# HV_DAC_8ch-DIOT.net
KiCad netlist of a schematic drawn in Altium Designer
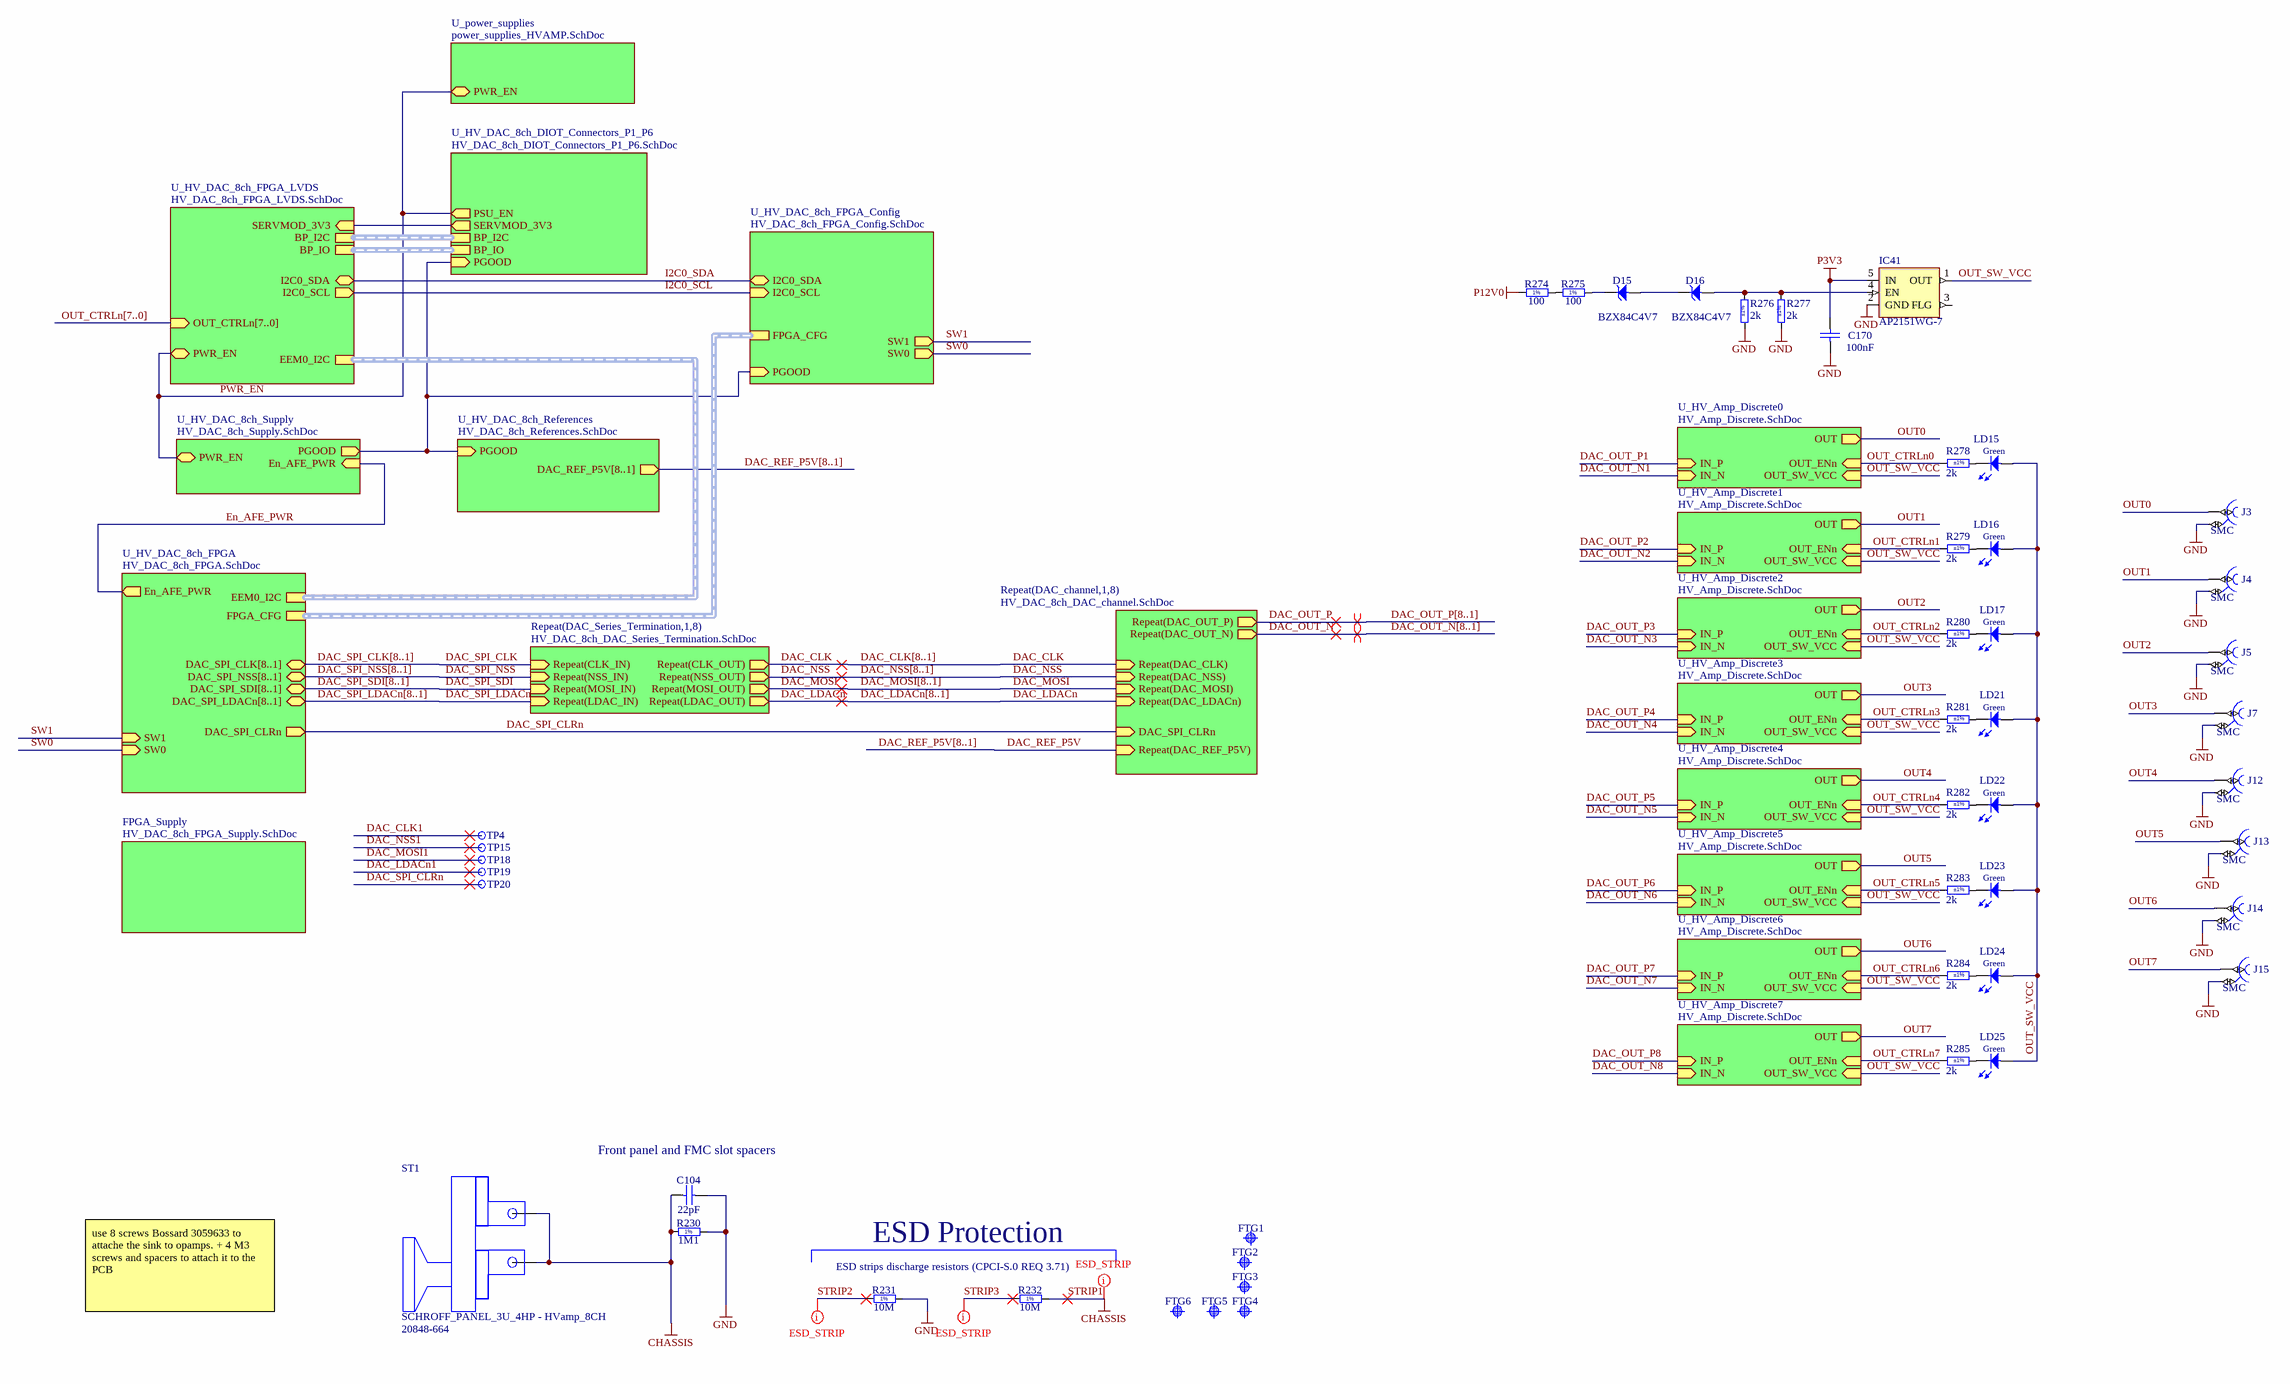
[diagram p0: HV_DAC_8ch-DIOT.schdoc]

(export (version "E")
  (design (tool "Eeschema 10.0.6"))
  (components
    (comp (ref "C104")
      (value "22pF")
      (footprint "CAPC1005X55N")
      (description "Non-polarised capacitor")
      (fields
        (field (name "PART NUMBER") "CC0402_22PF_50V_5%_C0G")
        (field (name "VOLTAGE") "50V")
        (field (name "AUTHOR") "CERN DEM JLC")
      )
      (libsource (lib "Capacitors") (part "Capacitor - non polarized"))
    )
    (comp (ref "C170")
      (value "100nF")
      (footprint "CAPC1005X55N")
      (description "Non-polarised capacitor")
      (fields
        (field (name "PART NUMBER") "CC0402_100NF_16V_10%_X5R")
        (field (name "VOLTAGE") "16V")
        (field (name "AUTHOR") "CERN DEM JLC")
      )
      (libsource (lib "Capacitors") (part "Capacitor - non polarized"))
    )
    (comp (ref "D15")
      (value "BZX84C4V7")
      (footprint "SOT95P240X130-3N")
      (description "Diode Zener Anode Pin 1 Cathode Pin 3 (Pas de pin 2)")
      (fields
        (field (name "VOLTAGE") "4V7")
        (field (name "POWER") "350mW")
        (field (name "AUTHOR") "CERN DEM JLC")
      )
      (libsource (lib "ICs And Semiconductors") (part "Diode Zener A1C3"))
    )
    (comp (ref "D16")
      (value "BZX84C4V7")
      (footprint "SOT95P240X130-3N")
      (description "Diode Zener Anode Pin 1 Cathode Pin 3 (Pas de pin 2)")
      (fields
        (field (name "VOLTAGE") "4V7")
        (field (name "POWER") "350mW")
        (field (name "AUTHOR") "CERN DEM JLC")
      )
      (libsource (lib "ICs And Semiconductors") (part "Diode Zener A1C3"))
    )
    (comp (ref "FTG1")
      (value "Use only in PCB")
      (footprint "FIDUCIAL_TOP_C100-200")
      (description "Fiducial Target")
      (fields (field (name "PART NUMBER") "FIDUCIAL_TARGET_C100-200") (field (name "AUTHOR") "CERN DEM JLC"))
      (libsource (lib "Eletro-mechanical") (part "Fiducial Target"))
    )
    (comp (ref "FTG2")
      (value "Use only in PCB")
      (footprint "FIDUCIAL_TOP_S100-200")
      (description "Fiducial Target")
      (fields (field (name "PART NUMBER") "FIDUCIAL_TARGET_S100-200") (field (name "AUTHOR") "CERN DEM JLC"))
      (libsource (lib "Eletro-mechanical") (part "Fiducial Target"))
    )
    (comp (ref "FTG3")
      (value "Use only in PCB")
      (footprint "FIDUCIAL_TOP_S100-200")
      (description "Fiducial Target")
      (fields (field (name "PART NUMBER") "FIDUCIAL_TARGET_S100-200") (field (name "AUTHOR") "CERN DEM JLC"))
      (libsource (lib "Eletro-mechanical") (part "Fiducial Target"))
    )
    (comp (ref "FTG4")
      (value "Use only in PCB")
      (footprint "FIDUCIAL_TOP_S100-200")
      (description "Fiducial Target")
      (fields (field (name "PART NUMBER") "FIDUCIAL_TARGET_S100-200") (field (name "AUTHOR") "CERN DEM JLC"))
      (libsource (lib "Eletro-mechanical") (part "Fiducial Target"))
    )
    (comp (ref "FTG5")
      (value "Use only in PCB")
      (footprint "FIDUCIAL_TOP_S100-200")
      (description "Fiducial Target")
      (fields (field (name "PART NUMBER") "FIDUCIAL_TARGET_S100-200") (field (name "AUTHOR") "CERN DEM JLC"))
      (libsource (lib "Eletro-mechanical") (part "Fiducial Target"))
    )
    (comp (ref "FTG6")
      (value "Use only in PCB")
      (footprint "FIDUCIAL_TOP_S100-200")
      (description "Fiducial Target")
      (fields (field (name "PART NUMBER") "FIDUCIAL_TARGET_S100-200") (field (name "AUTHOR") "CERN DEM JLC"))
      (libsource (lib "Eletro-mechanical") (part "Fiducial Target"))
    )
    (comp (ref "IC41")
      (value "AP2151WG-7")
      (footprint "SOT23-5")
      (description "0.5A SINGLE CHANNEL CURRENT- LIMITED POWER Switch")
      (libsource (lib "ICs_Analog_Interfaces") (part "IFC_AP2151"))
    )
    (comp (ref "J3")
      (value "SMC")
      (footprint "JOHNSON_131-6701-341")
      (fields
        (field (name "PART NUMBER") "JOHNSON_131-6701-341")
        (field (name "MANUFACTURER") "JOHNSON")
        (field (name "MANUFACTURER PART NUMBER") "131-6701-341")
        (field (name "AUTHOR") "CERN DEM JLC")
      )
      (libsource (lib "Connectors") (part "Coax_1Female_1Shield"))
    )
    (comp (ref "J4")
      (value "SMC")
      (footprint "JOHNSON_131-6701-341")
      (fields
        (field (name "PART NUMBER") "JOHNSON_131-6701-341")
        (field (name "MANUFACTURER") "JOHNSON")
        (field (name "MANUFACTURER PART NUMBER") "131-6701-341")
        (field (name "AUTHOR") "CERN DEM JLC")
      )
      (libsource (lib "Connectors") (part "Coax_1Female_1Shield"))
    )
    (comp (ref "J5")
      (value "SMC")
      (footprint "JOHNSON_131-6701-341")
      (fields
        (field (name "PART NUMBER") "JOHNSON_131-6701-341")
        (field (name "MANUFACTURER") "JOHNSON")
        (field (name "MANUFACTURER PART NUMBER") "131-6701-341")
        (field (name "AUTHOR") "CERN DEM JLC")
      )
      (libsource (lib "Connectors") (part "Coax_1Female_1Shield"))
    )
    (comp (ref "J7")
      (value "SMC")
      (footprint "JOHNSON_131-6701-341")
      (fields
        (field (name "PART NUMBER") "JOHNSON_131-6701-341")
        (field (name "MANUFACTURER") "JOHNSON")
        (field (name "MANUFACTURER PART NUMBER") "131-6701-341")
        (field (name "AUTHOR") "CERN DEM JLC")
      )
      (libsource (lib "Connectors") (part "Coax_1Female_1Shield"))
    )
    (comp (ref "J12")
      (value "SMC")
      (footprint "JOHNSON_131-6701-341")
      (fields
        (field (name "PART NUMBER") "JOHNSON_131-6701-341")
        (field (name "MANUFACTURER") "JOHNSON")
        (field (name "MANUFACTURER PART NUMBER") "131-6701-341")
        (field (name "AUTHOR") "CERN DEM JLC")
      )
      (libsource (lib "Connectors") (part "Coax_1Female_1Shield"))
    )
    (comp (ref "J13")
      (value "SMC")
      (footprint "JOHNSON_131-6701-341")
      (fields
        (field (name "PART NUMBER") "JOHNSON_131-6701-341")
        (field (name "MANUFACTURER") "JOHNSON")
        (field (name "MANUFACTURER PART NUMBER") "131-6701-341")
        (field (name "AUTHOR") "CERN DEM JLC")
      )
      (libsource (lib "Connectors") (part "Coax_1Female_1Shield"))
    )
    (comp (ref "J14")
      (value "SMC")
      (footprint "JOHNSON_131-6701-341")
      (fields
        (field (name "PART NUMBER") "JOHNSON_131-6701-341")
        (field (name "MANUFACTURER") "JOHNSON")
        (field (name "MANUFACTURER PART NUMBER") "131-6701-341")
        (field (name "AUTHOR") "CERN DEM JLC")
      )
      (libsource (lib "Connectors") (part "Coax_1Female_1Shield"))
    )
    (comp (ref "J15")
      (value "SMC")
      (footprint "JOHNSON_131-6701-341")
      (fields
        (field (name "PART NUMBER") "JOHNSON_131-6701-341")
        (field (name "MANUFACTURER") "JOHNSON")
        (field (name "MANUFACTURER PART NUMBER") "131-6701-341")
        (field (name "AUTHOR") "CERN DEM JLC")
      )
      (libsource (lib "Connectors") (part "Coax_1Female_1Shield"))
    )
    (comp (ref "LD15")
      (value "Green")
      (footprint "LED_AVAGO_HSME-C120")
      (description "LED Green 1C 2A")
      (fields
        (field (name "PART NUMBER") "LED_AVAGO_HSME-C120")
        (field (name "MANUFACTURER") "AVAGO TECHNOLOGIES")
        (field (name "AUTHOR") "CERN DEM JMW")
      )
      (libsource (lib "ICs And Semiconductors") (part "LED Green 1C 2A"))
    )
    (comp (ref "LD16")
      (value "Green")
      (footprint "LED_AVAGO_HSME-C120")
      (description "LED Green 1C 2A")
      (fields
        (field (name "PART NUMBER") "LED_AVAGO_HSME-C120")
        (field (name "MANUFACTURER") "AVAGO TECHNOLOGIES")
        (field (name "AUTHOR") "CERN DEM JMW")
      )
      (libsource (lib "ICs And Semiconductors") (part "LED Green 1C 2A"))
    )
    (comp (ref "LD17")
      (value "Green")
      (footprint "LED_AVAGO_HSME-C120")
      (description "LED Green 1C 2A")
      (fields
        (field (name "PART NUMBER") "LED_AVAGO_HSME-C120")
        (field (name "MANUFACTURER") "AVAGO TECHNOLOGIES")
        (field (name "AUTHOR") "CERN DEM JMW")
      )
      (libsource (lib "ICs And Semiconductors") (part "LED Green 1C 2A"))
    )
    (comp (ref "LD21")
      (value "Green")
      (footprint "LED_AVAGO_HSME-C120")
      (description "LED Green 1C 2A")
      (fields
        (field (name "PART NUMBER") "LED_AVAGO_HSME-C120")
        (field (name "MANUFACTURER") "AVAGO TECHNOLOGIES")
        (field (name "AUTHOR") "CERN DEM JMW")
      )
      (libsource (lib "ICs And Semiconductors") (part "LED Green 1C 2A"))
    )
    (comp (ref "LD22")
      (value "Green")
      (footprint "LED_AVAGO_HSME-C120")
      (description "LED Green 1C 2A")
      (fields
        (field (name "PART NUMBER") "LED_AVAGO_HSME-C120")
        (field (name "MANUFACTURER") "AVAGO TECHNOLOGIES")
        (field (name "AUTHOR") "CERN DEM JMW")
      )
      (libsource (lib "ICs And Semiconductors") (part "LED Green 1C 2A"))
    )
    (comp (ref "LD23")
      (value "Green")
      (footprint "LED_AVAGO_HSME-C120")
      (description "LED Green 1C 2A")
      (fields
        (field (name "PART NUMBER") "LED_AVAGO_HSME-C120")
        (field (name "MANUFACTURER") "AVAGO TECHNOLOGIES")
        (field (name "AUTHOR") "CERN DEM JMW")
      )
      (libsource (lib "ICs And Semiconductors") (part "LED Green 1C 2A"))
    )
    (comp (ref "LD24")
      (value "Green")
      (footprint "LED_AVAGO_HSME-C120")
      (description "LED Green 1C 2A")
      (fields
        (field (name "PART NUMBER") "LED_AVAGO_HSME-C120")
        (field (name "MANUFACTURER") "AVAGO TECHNOLOGIES")
        (field (name "AUTHOR") "CERN DEM JMW")
      )
      (libsource (lib "ICs And Semiconductors") (part "LED Green 1C 2A"))
    )
    (comp (ref "LD25")
      (value "Green")
      (footprint "LED_AVAGO_HSME-C120")
      (description "LED Green 1C 2A")
      (fields
        (field (name "PART NUMBER") "LED_AVAGO_HSME-C120")
        (field (name "MANUFACTURER") "AVAGO TECHNOLOGIES")
        (field (name "AUTHOR") "CERN DEM JMW")
      )
      (libsource (lib "ICs And Semiconductors") (part "LED Green 1C 2A"))
    )
    (comp (ref "R230")
      (value "1M1")
      (footprint "RESC2012X60N")
      (description "Resistor - 1%")
      (fields
        (field (name "PART NUMBER") "R0805_1M1_1%_0.125W_100PPM")
        (field (name "POWER") "0.125W")
        (field (name "AUTHOR") "CERN DEM JLC")
      )
      (libsource (lib "") (part "Resistor - 1%_1"))
    )
    (comp (ref "R231")
      (value "10M")
      (footprint "RESC2113X55N")
      (description "Resistor - 1%")
      (fields
        (field (name "PART NUMBER") "R0805_10M_1%_0.125W_100PPM_VISHAY_CRCW e3")
        (field (name "POWER") "0.125W")
        (field (name "AUTHOR") "CERN DEM BC")
      )
      (libsource (lib "") (part "Resistor - 1%_1"))
    )
    (comp (ref "R232")
      (value "10M")
      (footprint "RESC2113X55N")
      (description "Resistor - 1%")
      (fields
        (field (name "PART NUMBER") "R0805_10M_1%_0.125W_100PPM_VISHAY_CRCW e3")
        (field (name "POWER") "0.125W")
        (field (name "AUTHOR") "CERN DEM BC")
      )
      (libsource (lib "") (part "Resistor - 1%_1"))
    )
    (comp (ref "R274")
      (value "100")
      (footprint "RESC1005X40N")
      (description "Resistor - 1%")
      (fields
        (field (name "PART NUMBER") "R0402_100R_1%_0.0625W_100PPM")
        (field (name "POWER") "0.0625W")
        (field (name "AUTHOR") "CERN DEM JLC")
      )
      (libsource (lib "Resistors") (part "Resistor - 1%"))
    )
    (comp (ref "R275")
      (value "100")
      (footprint "RESC1005X40N")
      (description "Resistor - 1%")
      (fields
        (field (name "PART NUMBER") "R0402_100R_1%_0.0625W_100PPM")
        (field (name "POWER") "0.0625W")
        (field (name "AUTHOR") "CERN DEM JLC")
      )
      (libsource (lib "Resistors") (part "Resistor - 1%"))
    )
    (comp (ref "R276")
      (value "2k")
      (footprint "RESC1005X40N")
      (description "Resistor - 1%")
      (fields
        (field (name "PART NUMBER") "R0402_2K_1%_0.0625W_100PPM")
        (field (name "POWER") "0.0625W")
        (field (name "TOLERANCE") "±1%")
        (field (name "AUTHOR") "CERN DEM JLC")
      )
      (libsource (lib "Resistors") (part "Resistor - 1%"))
    )
    (comp (ref "R277")
      (value "2k")
      (footprint "RESC1005X40N")
      (description "Resistor - 1%")
      (fields
        (field (name "PART NUMBER") "R0402_2K_1%_0.0625W_100PPM")
        (field (name "POWER") "0.0625W")
        (field (name "TOLERANCE") "±1%")
        (field (name "AUTHOR") "CERN DEM JLC")
      )
      (libsource (lib "Resistors") (part "Resistor - 1%"))
    )
    (comp (ref "R278")
      (value "2k")
      (footprint "RESC1005X40N")
      (description "Resistor - 1%")
      (fields
        (field (name "PART NUMBER") "R0402_2K_1%_0.0625W_100PPM")
        (field (name "POWER") "0.0625W")
        (field (name "TOLERANCE") "±1%")
        (field (name "AUTHOR") "CERN DEM JLC")
      )
      (libsource (lib "Resistors") (part "Resistor - 1%"))
    )
    (comp (ref "R279")
      (value "2k")
      (footprint "RESC1005X40N")
      (description "Resistor - 1%")
      (fields
        (field (name "PART NUMBER") "R0402_2K_1%_0.0625W_100PPM")
        (field (name "POWER") "0.0625W")
        (field (name "TOLERANCE") "±1%")
        (field (name "AUTHOR") "CERN DEM JLC")
      )
      (libsource (lib "Resistors") (part "Resistor - 1%"))
    )
    (comp (ref "R280")
      (value "2k")
      (footprint "RESC1005X40N")
      (description "Resistor - 1%")
      (fields
        (field (name "PART NUMBER") "R0402_2K_1%_0.0625W_100PPM")
        (field (name "POWER") "0.0625W")
        (field (name "TOLERANCE") "±1%")
        (field (name "AUTHOR") "CERN DEM JLC")
      )
      (libsource (lib "Resistors") (part "Resistor - 1%"))
    )
    (comp (ref "R281")
      (value "2k")
      (footprint "RESC1005X40N")
      (description "Resistor - 1%")
      (fields
        (field (name "PART NUMBER") "R0402_2K_1%_0.0625W_100PPM")
        (field (name "POWER") "0.0625W")
        (field (name "TOLERANCE") "±1%")
        (field (name "AUTHOR") "CERN DEM JLC")
      )
      (libsource (lib "Resistors") (part "Resistor - 1%"))
    )
    (comp (ref "R282")
      (value "2k")
      (footprint "RESC1005X40N")
      (description "Resistor - 1%")
      (fields
        (field (name "PART NUMBER") "R0402_2K_1%_0.0625W_100PPM")
        (field (name "POWER") "0.0625W")
        (field (name "TOLERANCE") "±1%")
        (field (name "AUTHOR") "CERN DEM JLC")
      )
      (libsource (lib "Resistors") (part "Resistor - 1%"))
    )
    (comp (ref "R283")
      (value "2k")
      (footprint "RESC1005X40N")
      (description "Resistor - 1%")
      (fields
        (field (name "PART NUMBER") "R0402_2K_1%_0.0625W_100PPM")
        (field (name "POWER") "0.0625W")
        (field (name "TOLERANCE") "±1%")
        (field (name "AUTHOR") "CERN DEM JLC")
      )
      (libsource (lib "Resistors") (part "Resistor - 1%"))
    )
    (comp (ref "R284")
      (value "2k")
      (footprint "RESC1005X40N")
      (description "Resistor - 1%")
      (fields
        (field (name "PART NUMBER") "R0402_2K_1%_0.0625W_100PPM")
        (field (name "POWER") "0.0625W")
        (field (name "TOLERANCE") "±1%")
        (field (name "AUTHOR") "CERN DEM JLC")
      )
      (libsource (lib "Resistors") (part "Resistor - 1%"))
    )
    (comp (ref "R285")
      (value "2k")
      (footprint "RESC1005X40N")
      (description "Resistor - 1%")
      (fields
        (field (name "PART NUMBER") "R0402_2K_1%_0.0625W_100PPM")
        (field (name "POWER") "0.0625W")
        (field (name "TOLERANCE") "±1%")
        (field (name "AUTHOR") "CERN DEM JLC")
      )
      (libsource (lib "Resistors") (part "Resistor - 1%"))
    )
    (comp (ref "ST1")
      (value "SCHROFF_PANEL_3U_4HP - HVamp_8CH")
      (footprint "SCHROFF_PANEL_3U_4HP - HVamp_8CH")
      (description "Schroff 3HP 4U EUROCARD Panel")
      (fields
        (field (name "MANUFACTURER") "Schroff")
        (field (name "MANUFACTURER PART NUMBER") "20818-017")
        (field (name "MANUFACTURER PART NUMBER 2") "20848-664")
      )
      (libsource (lib "Mechanical") (part "SCHROFF_PANEL_3U_4HP - HVamp_8CH"))
    )
    (comp (ref "TP4")
      (value "Test Point")
      (footprint "TPS127")
      (fields (field (name "PART NUMBER") "SMD_PAD_1.27X1.27MM") (field (name "AUTHOR") "CERN DEM JLC"))
      (libsource (lib "Eletro-mechanical") (part "Test Point"))
    )
    (comp (ref "TP15")
      (value "Test Point")
      (footprint "TPS127")
      (fields (field (name "PART NUMBER") "SMD_PAD_1.27X1.27MM") (field (name "AUTHOR") "CERN DEM JLC"))
      (libsource (lib "Eletro-mechanical") (part "Test Point"))
    )
    (comp (ref "TP18")
      (value "Test Point")
      (footprint "TPS127")
      (fields (field (name "PART NUMBER") "SMD_PAD_1.27X1.27MM") (field (name "AUTHOR") "CERN DEM JLC"))
      (libsource (lib "Eletro-mechanical") (part "Test Point"))
    )
    (comp (ref "TP19")
      (value "Test Point")
      (footprint "TPS127")
      (fields (field (name "PART NUMBER") "SMD_PAD_1.27X1.27MM") (field (name "AUTHOR") "CERN DEM JLC"))
      (libsource (lib "Eletro-mechanical") (part "Test Point"))
    )
    (comp (ref "TP20")
      (value "Test Point")
      (footprint "TPS127")
      (fields (field (name "PART NUMBER") "SMD_PAD_1.27X1.27MM") (field (name "AUTHOR") "CERN DEM JLC"))
      (libsource (lib "Eletro-mechanical") (part "Test Point"))
    )
  )
  (nets
    (net (code "72") (name "/DAC_CLK1") (class "Default")
      (node (ref "TP4") (pin "1") (pinfunction "1_1") (pintype "bidirectional"))
    )
    (net (code "75") (name "/DAC_LDACn1") (class "Default")
      (node (ref "TP19") (pin "1") (pinfunction "1_1") (pintype "bidirectional"))
    )
    (net (code "78") (name "/DAC_MOSI1") (class "Default")
      (node (ref "TP18") (pin "1") (pinfunction "1_1") (pintype "bidirectional"))
    )
    (net (code "81") (name "/DAC_NSS1") (class "Default")
      (node (ref "TP15") (pin "1") (pinfunction "1_1") (pintype "bidirectional"))
    )
    (net (code "107") (name "/DAC_SPI_CLRn") (class "Default")
      (node (ref "TP20") (pin "1") (pinfunction "1_1") (pintype "bidirectional"))
    )
    (net (code "119") (name "/OUT0") (class "Default")
      (node (ref "J3") (pin "1") (pinfunction "1_1") (pintype "bidirectional"))
    )
    (net (code "120") (name "/OUT1") (class "Default")
      (node (ref "J4") (pin "1") (pinfunction "1_1") (pintype "bidirectional"))
    )
    (net (code "121") (name "/OUT2") (class "Default")
      (node (ref "J5") (pin "1") (pinfunction "1_1") (pintype "bidirectional"))
    )
    (net (code "122") (name "/OUT3") (class "Default")
      (node (ref "J7") (pin "1") (pinfunction "1_1") (pintype "bidirectional"))
    )
    (net (code "123") (name "/OUT4") (class "Default")
      (node (ref "J12") (pin "1") (pinfunction "1_1") (pintype "bidirectional"))
    )
    (net (code "124") (name "/OUT5") (class "Default")
      (node (ref "J13") (pin "1") (pinfunction "1_1") (pintype "bidirectional"))
    )
    (net (code "125") (name "/OUT6") (class "Default")
      (node (ref "J14") (pin "1") (pinfunction "1_1") (pintype "bidirectional"))
    )
    (net (code "126") (name "/OUT7") (class "Default")
      (node (ref "J15") (pin "1") (pinfunction "1_1") (pintype "bidirectional"))
    )
    (net (code "127") (name "/OUT_CTRLn0") (class "Default")
      (node (ref "R278") (pin "2") (pinfunction "2_2") (pintype "passive"))
    )
    (net (code "128") (name "/OUT_CTRLn1") (class "Default")
      (node (ref "R279") (pin "2") (pinfunction "2_2") (pintype "passive"))
    )
    (net (code "129") (name "/OUT_CTRLn2") (class "Default")
      (node (ref "R280") (pin "2") (pinfunction "2_2") (pintype "passive"))
    )
    (net (code "130") (name "/OUT_CTRLn3") (class "Default")
      (node (ref "R281") (pin "2") (pinfunction "2_2") (pintype "passive"))
    )
    (net (code "131") (name "/OUT_CTRLn4") (class "Default")
      (node (ref "R282") (pin "2") (pinfunction "2_2") (pintype "passive"))
    )
    (net (code "132") (name "/OUT_CTRLn5") (class "Default")
      (node (ref "R283") (pin "2") (pinfunction "2_2") (pintype "passive"))
    )
    (net (code "133") (name "/OUT_CTRLn6") (class "Default")
      (node (ref "R284") (pin "2") (pinfunction "2_2") (pintype "passive"))
    )
    (net (code "134") (name "/OUT_CTRLn7") (class "Default")
      (node (ref "R285") (pin "2") (pinfunction "2_2") (pintype "passive"))
    )
    (net (code "136") (name "/OUT_SW_VCC") (class "Default")
      (node (ref "IC41") (pin "1") (pinfunction "OUT_1") (pintype "output"))
      (node (ref "LD15") (pin "2") (pinfunction "A_2") (pintype "passive"))
      (node (ref "LD16") (pin "2") (pinfunction "A_2") (pintype "passive"))
      (node (ref "LD17") (pin "2") (pinfunction "A_2") (pintype "passive"))
      (node (ref "LD21") (pin "2") (pinfunction "A_2") (pintype "passive"))
      (node (ref "LD22") (pin "2") (pinfunction "A_2") (pintype "passive"))
      (node (ref "LD23") (pin "2") (pinfunction "A_2") (pintype "passive"))
      (node (ref "LD24") (pin "2") (pinfunction "A_2") (pintype "passive"))
      (node (ref "LD25") (pin "2") (pinfunction "A_2") (pintype "passive"))
    )
    (net (code "141") (name "/STRIP2") (class "Default")
      (node (ref "R231") (pin "1") (pinfunction "1_1") (pintype "passive+no_connect"))
    )
    (net (code "142") (name "/STRIP3") (class "Default")
      (node (ref "R232") (pin "1") (pinfunction "1_1") (pintype "passive+no_connect"))
    )
    (net (code "145") (name "CHASSIS") (class "Default")
      (node (ref "C104") (pin "1") (pinfunction "1_1") (pintype "passive"))
      (node (ref "R230") (pin "1") (pinfunction "1_1") (pintype "passive"))
      (node (ref "R232") (pin "2") (pinfunction "2_2") (pintype "passive"))
      (node (ref "ST1") (pin "0") (pinfunction "0_0") (pintype "passive"))
      (node (ref "ST1") (pin "1") (pinfunction "1_1") (pintype "passive"))
    )
    (net (code "146") (name "GND") (class "Default")
      (node (ref "C104") (pin "2") (pinfunction "2_2") (pintype "passive"))
      (node (ref "C170") (pin "1") (pinfunction "1_1") (pintype "passive"))
      (node (ref "IC41") (pin "2") (pinfunction "GND_2") (pintype "power_in"))
      (node (ref "J12") (pin "2") (pinfunction "2_2") (pintype "bidirectional"))
      (node (ref "J13") (pin "2") (pinfunction "2_2") (pintype "bidirectional"))
      (node (ref "J14") (pin "2") (pinfunction "2_2") (pintype "bidirectional"))
      (node (ref "J15") (pin "2") (pinfunction "2_2") (pintype "bidirectional"))
      (node (ref "J3") (pin "2") (pinfunction "2_2") (pintype "bidirectional"))
      (node (ref "J4") (pin "2") (pinfunction "2_2") (pintype "bidirectional"))
      (node (ref "J5") (pin "2") (pinfunction "2_2") (pintype "bidirectional"))
      (node (ref "J7") (pin "2") (pinfunction "2_2") (pintype "bidirectional"))
      (node (ref "R230") (pin "2") (pinfunction "2_2") (pintype "passive"))
      (node (ref "R231") (pin "2") (pinfunction "2_2") (pintype "passive"))
      (node (ref "R276") (pin "2") (pinfunction "2_2") (pintype "passive"))
      (node (ref "R277") (pin "2") (pinfunction "2_2") (pintype "passive"))
    )
    (net (code "147") (name "Net-(D15-A)") (class "Default")
      (node (ref "D15") (pin "1") (pinfunction "A_1") (pintype "passive"))
      (node (ref "D16") (pin "3") (pinfunction "C_3") (pintype "passive"))
    )
    (net (code "148") (name "Net-(D15-C)") (class "Default")
      (node (ref "D15") (pin "3") (pinfunction "C_3") (pintype "passive"))
      (node (ref "R275") (pin "2") (pinfunction "2_2") (pintype "passive"))
    )
    (net (code "149") (name "Net-(D16-A)") (class "Default")
      (node (ref "D16") (pin "1") (pinfunction "A_1") (pintype "passive"))
      (node (ref "IC41") (pin "4") (pinfunction "EN_4") (pintype "input"))
      (node (ref "R276") (pin "1") (pinfunction "1_1") (pintype "passive"))
      (node (ref "R277") (pin "1") (pinfunction "1_1") (pintype "passive"))
    )
    (net (code "150") (name "Net-(LD15-C)") (class "Default")
      (node (ref "LD15") (pin "1") (pinfunction "C_1") (pintype "passive"))
      (node (ref "R278") (pin "1") (pinfunction "1_1") (pintype "passive"))
    )
    (net (code "151") (name "Net-(LD16-C)") (class "Default")
      (node (ref "LD16") (pin "1") (pinfunction "C_1") (pintype "passive"))
      (node (ref "R279") (pin "1") (pinfunction "1_1") (pintype "passive"))
    )
    (net (code "152") (name "Net-(LD17-C)") (class "Default")
      (node (ref "LD17") (pin "1") (pinfunction "C_1") (pintype "passive"))
      (node (ref "R280") (pin "1") (pinfunction "1_1") (pintype "passive"))
    )
    (net (code "153") (name "Net-(LD21-C)") (class "Default")
      (node (ref "LD21") (pin "1") (pinfunction "C_1") (pintype "passive"))
      (node (ref "R281") (pin "1") (pinfunction "1_1") (pintype "passive"))
    )
    (net (code "154") (name "Net-(LD22-C)") (class "Default")
      (node (ref "LD22") (pin "1") (pinfunction "C_1") (pintype "passive"))
      (node (ref "R282") (pin "1") (pinfunction "1_1") (pintype "passive"))
    )
    (net (code "155") (name "Net-(LD23-C)") (class "Default")
      (node (ref "LD23") (pin "1") (pinfunction "C_1") (pintype "passive"))
      (node (ref "R283") (pin "1") (pinfunction "1_1") (pintype "passive"))
    )
    (net (code "156") (name "Net-(LD24-C)") (class "Default")
      (node (ref "LD24") (pin "1") (pinfunction "C_1") (pintype "passive"))
      (node (ref "R284") (pin "1") (pinfunction "1_1") (pintype "passive"))
    )
    (net (code "157") (name "Net-(LD25-C)") (class "Default")
      (node (ref "LD25") (pin "1") (pinfunction "C_1") (pintype "passive"))
      (node (ref "R285") (pin "1") (pinfunction "1_1") (pintype "passive"))
    )
    (net (code "158") (name "Net-(R274-Pad2)") (class "Default")
      (node (ref "R274") (pin "2") (pinfunction "2_2") (pintype "passive"))
      (node (ref "R275") (pin "1") (pinfunction "1_1") (pintype "passive"))
    )
    (net (code "159") (name "P3V3") (class "Default")
      (node (ref "C170") (pin "2") (pinfunction "2_2") (pintype "passive"))
      (node (ref "IC41") (pin "5") (pinfunction "IN_5") (pintype "power_in"))
    )
    (net (code "160") (name "P12V0") (class "Default")
      (node (ref "R274") (pin "1") (pinfunction "1_1") (pintype "passive"))
    )
    (net (code "161") (name "unconnected-(IC41-FLG-Pad3)") (class "Default")
      (node (ref "IC41") (pin "3") (pinfunction "FLG_3") (pintype "output"))
    )
  )
)
